# infinity-mirror-clock.net
KiCad netlist of a schematic drawn in EAGLE
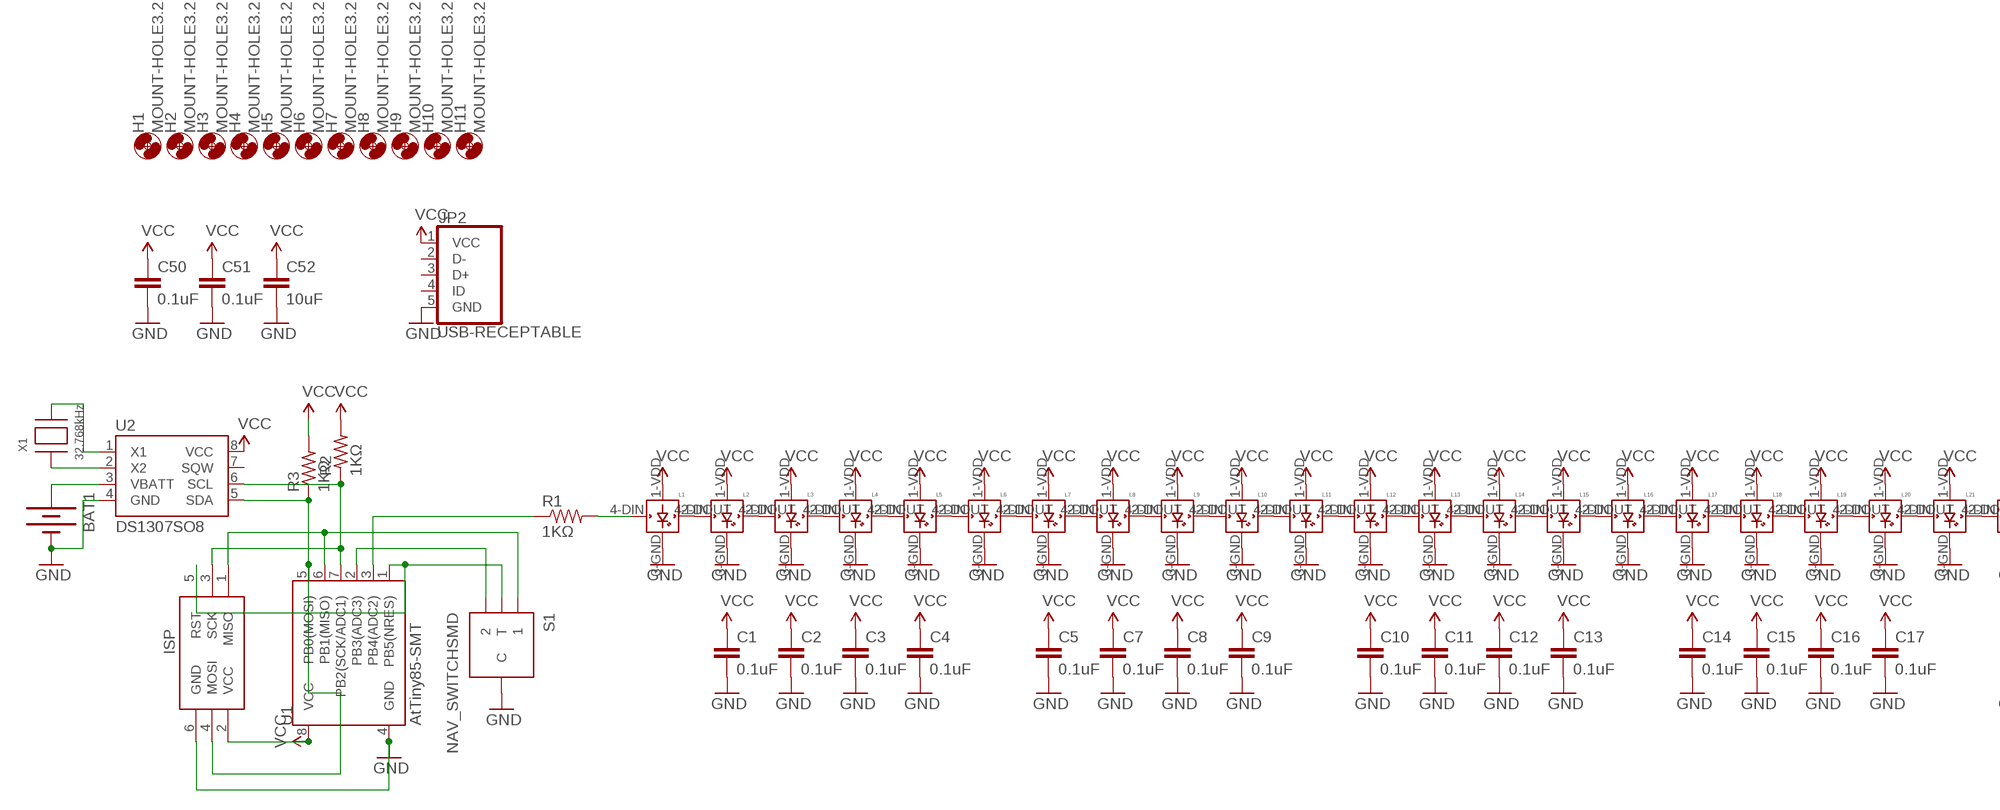
[diagram p0: schematic, sheet 1, part 1 of 2]
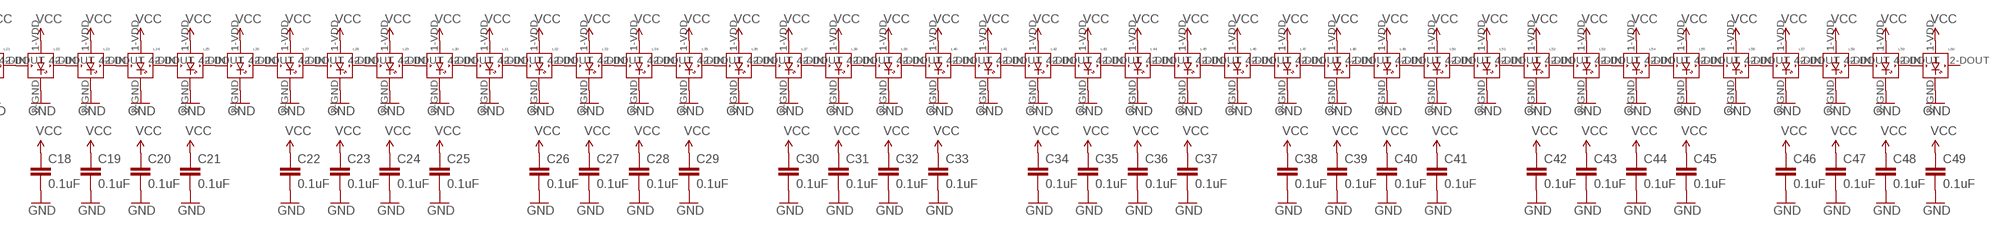
[diagram p1: schematic, sheet 1, part 2 of 2]

(export (version "E")
  (design (tool "Eeschema 10.0.6"))
  (components
    (comp (ref "BAT1")
      (value "BATTERY12MM")
      (footprint "eagle-import:BATTCON_12MM")
      (libsource (lib "eagle-import") (part "BATTERY12MM"))
    )
    (comp (ref "C1")
      (value "0.1uF")
      (footprint "eagle-import:0603-CAP")
      (libsource (lib "eagle-import") (part "0.1UF-25V-5%(0603)"))
    )
    (comp (ref "C2")
      (value "0.1uF")
      (footprint "eagle-import:0603-CAP")
      (libsource (lib "eagle-import") (part "0.1UF-25V-5%(0603)"))
    )
    (comp (ref "C3")
      (value "0.1uF")
      (footprint "eagle-import:0603-CAP")
      (libsource (lib "eagle-import") (part "0.1UF-25V-5%(0603)"))
    )
    (comp (ref "C4")
      (value "0.1uF")
      (footprint "eagle-import:0603-CAP")
      (libsource (lib "eagle-import") (part "0.1UF-25V-5%(0603)"))
    )
    (comp (ref "C5")
      (value "0.1uF")
      (footprint "eagle-import:0603-CAP")
      (libsource (lib "eagle-import") (part "0.1UF-25V-5%(0603)"))
    )
    (comp (ref "C7")
      (value "0.1uF")
      (footprint "eagle-import:0603-CAP")
      (libsource (lib "eagle-import") (part "0.1UF-25V-5%(0603)"))
    )
    (comp (ref "C8")
      (value "0.1uF")
      (footprint "eagle-import:0603-CAP")
      (libsource (lib "eagle-import") (part "0.1UF-25V-5%(0603)"))
    )
    (comp (ref "C9")
      (value "0.1uF")
      (footprint "eagle-import:0603-CAP")
      (libsource (lib "eagle-import") (part "0.1UF-25V-5%(0603)"))
    )
    (comp (ref "C10")
      (value "0.1uF")
      (footprint "eagle-import:0603-CAP")
      (libsource (lib "eagle-import") (part "0.1UF-25V-5%(0603)"))
    )
    (comp (ref "C11")
      (value "0.1uF")
      (footprint "eagle-import:0603-CAP")
      (libsource (lib "eagle-import") (part "0.1UF-25V-5%(0603)"))
    )
    (comp (ref "C12")
      (value "0.1uF")
      (footprint "eagle-import:0603-CAP")
      (libsource (lib "eagle-import") (part "0.1UF-25V-5%(0603)"))
    )
    (comp (ref "C13")
      (value "0.1uF")
      (footprint "eagle-import:0603-CAP")
      (libsource (lib "eagle-import") (part "0.1UF-25V-5%(0603)"))
    )
    (comp (ref "C14")
      (value "0.1uF")
      (footprint "eagle-import:0603-CAP")
      (libsource (lib "eagle-import") (part "0.1UF-25V-5%(0603)"))
    )
    (comp (ref "C15")
      (value "0.1uF")
      (footprint "eagle-import:0603-CAP")
      (libsource (lib "eagle-import") (part "0.1UF-25V-5%(0603)"))
    )
    (comp (ref "C16")
      (value "0.1uF")
      (footprint "eagle-import:0603-CAP")
      (libsource (lib "eagle-import") (part "0.1UF-25V-5%(0603)"))
    )
    (comp (ref "C17")
      (value "0.1uF")
      (footprint "eagle-import:0603-CAP")
      (libsource (lib "eagle-import") (part "0.1UF-25V-5%(0603)"))
    )
    (comp (ref "C18")
      (value "0.1uF")
      (footprint "eagle-import:0603-CAP")
      (libsource (lib "eagle-import") (part "0.1UF-25V-5%(0603)"))
    )
    (comp (ref "C19")
      (value "0.1uF")
      (footprint "eagle-import:0603-CAP")
      (libsource (lib "eagle-import") (part "0.1UF-25V-5%(0603)"))
    )
    (comp (ref "C20")
      (value "0.1uF")
      (footprint "eagle-import:0603-CAP")
      (libsource (lib "eagle-import") (part "0.1UF-25V-5%(0603)"))
    )
    (comp (ref "C21")
      (value "0.1uF")
      (footprint "eagle-import:0603-CAP")
      (libsource (lib "eagle-import") (part "0.1UF-25V-5%(0603)"))
    )
    (comp (ref "C22")
      (value "0.1uF")
      (footprint "eagle-import:0603-CAP")
      (libsource (lib "eagle-import") (part "0.1UF-25V-5%(0603)"))
    )
    (comp (ref "C23")
      (value "0.1uF")
      (footprint "eagle-import:0603-CAP")
      (libsource (lib "eagle-import") (part "0.1UF-25V-5%(0603)"))
    )
    (comp (ref "C24")
      (value "0.1uF")
      (footprint "eagle-import:0603-CAP")
      (libsource (lib "eagle-import") (part "0.1UF-25V-5%(0603)"))
    )
    (comp (ref "C25")
      (value "0.1uF")
      (footprint "eagle-import:0603-CAP")
      (libsource (lib "eagle-import") (part "0.1UF-25V-5%(0603)"))
    )
    (comp (ref "C26")
      (value "0.1uF")
      (footprint "eagle-import:0603-CAP")
      (libsource (lib "eagle-import") (part "0.1UF-25V-5%(0603)"))
    )
    (comp (ref "C27")
      (value "0.1uF")
      (footprint "eagle-import:0603-CAP")
      (libsource (lib "eagle-import") (part "0.1UF-25V-5%(0603)"))
    )
    (comp (ref "C28")
      (value "0.1uF")
      (footprint "eagle-import:0603-CAP")
      (libsource (lib "eagle-import") (part "0.1UF-25V-5%(0603)"))
    )
    (comp (ref "C29")
      (value "0.1uF")
      (footprint "eagle-import:0603-CAP")
      (libsource (lib "eagle-import") (part "0.1UF-25V-5%(0603)"))
    )
    (comp (ref "C30")
      (value "0.1uF")
      (footprint "eagle-import:0603-CAP")
      (libsource (lib "eagle-import") (part "0.1UF-25V-5%(0603)"))
    )
    (comp (ref "C31")
      (value "0.1uF")
      (footprint "eagle-import:0603-CAP")
      (libsource (lib "eagle-import") (part "0.1UF-25V-5%(0603)"))
    )
    (comp (ref "C32")
      (value "0.1uF")
      (footprint "eagle-import:0603-CAP")
      (libsource (lib "eagle-import") (part "0.1UF-25V-5%(0603)"))
    )
    (comp (ref "C33")
      (value "0.1uF")
      (footprint "eagle-import:0603-CAP")
      (libsource (lib "eagle-import") (part "0.1UF-25V-5%(0603)"))
    )
    (comp (ref "C34")
      (value "0.1uF")
      (footprint "eagle-import:0603-CAP")
      (libsource (lib "eagle-import") (part "0.1UF-25V-5%(0603)"))
    )
    (comp (ref "C35")
      (value "0.1uF")
      (footprint "eagle-import:0603-CAP")
      (libsource (lib "eagle-import") (part "0.1UF-25V-5%(0603)"))
    )
    (comp (ref "C36")
      (value "0.1uF")
      (footprint "eagle-import:0603-CAP")
      (libsource (lib "eagle-import") (part "0.1UF-25V-5%(0603)"))
    )
    (comp (ref "C37")
      (value "0.1uF")
      (footprint "eagle-import:0603-CAP")
      (libsource (lib "eagle-import") (part "0.1UF-25V-5%(0603)"))
    )
    (comp (ref "C38")
      (value "0.1uF")
      (footprint "eagle-import:0603-CAP")
      (libsource (lib "eagle-import") (part "0.1UF-25V-5%(0603)"))
    )
    (comp (ref "C39")
      (value "0.1uF")
      (footprint "eagle-import:0603-CAP")
      (libsource (lib "eagle-import") (part "0.1UF-25V-5%(0603)"))
    )
    (comp (ref "C40")
      (value "0.1uF")
      (footprint "eagle-import:0603-CAP")
      (libsource (lib "eagle-import") (part "0.1UF-25V-5%(0603)"))
    )
    (comp (ref "C41")
      (value "0.1uF")
      (footprint "eagle-import:0603-CAP")
      (libsource (lib "eagle-import") (part "0.1UF-25V-5%(0603)"))
    )
    (comp (ref "C42")
      (value "0.1uF")
      (footprint "eagle-import:0603-CAP")
      (libsource (lib "eagle-import") (part "0.1UF-25V-5%(0603)"))
    )
    (comp (ref "C43")
      (value "0.1uF")
      (footprint "eagle-import:0603-CAP")
      (libsource (lib "eagle-import") (part "0.1UF-25V-5%(0603)"))
    )
    (comp (ref "C44")
      (value "0.1uF")
      (footprint "eagle-import:0603-CAP")
      (libsource (lib "eagle-import") (part "0.1UF-25V-5%(0603)"))
    )
    (comp (ref "C45")
      (value "0.1uF")
      (footprint "eagle-import:0603-CAP")
      (libsource (lib "eagle-import") (part "0.1UF-25V-5%(0603)"))
    )
    (comp (ref "C46")
      (value "0.1uF")
      (footprint "eagle-import:0603-CAP")
      (libsource (lib "eagle-import") (part "0.1UF-25V-5%(0603)"))
    )
    (comp (ref "C47")
      (value "0.1uF")
      (footprint "eagle-import:0603-CAP")
      (libsource (lib "eagle-import") (part "0.1UF-25V-5%(0603)"))
    )
    (comp (ref "C48")
      (value "0.1uF")
      (footprint "eagle-import:0603-CAP")
      (libsource (lib "eagle-import") (part "0.1UF-25V-5%(0603)"))
    )
    (comp (ref "C49")
      (value "0.1uF")
      (footprint "eagle-import:0603-CAP")
      (libsource (lib "eagle-import") (part "0.1UF-25V-5%(0603)"))
    )
    (comp (ref "C50")
      (value "0.1uF")
      (footprint "eagle-import:0603-CAP")
      (libsource (lib "eagle-import") (part "0.1UF-25V-5%(0603)"))
    )
    (comp (ref "C51")
      (value "0.1uF")
      (footprint "eagle-import:0603-CAP")
      (libsource (lib "eagle-import") (part "0.1UF-25V-5%(0603)"))
    )
    (comp (ref "C52")
      (value "10uF")
      (footprint "eagle-import:0603-CAP")
      (libsource (lib "eagle-import") (part "10UF-6.3V-20%(0603)"))
    )
    (comp (ref "H1")
      (value "MOUNT-HOLE3.2")
      (footprint "eagle-import:3,2")
      (libsource (lib "eagle-import") (part "MOUNT-HOLE3.2"))
    )
    (comp (ref "H2")
      (value "MOUNT-HOLE3.2")
      (footprint "eagle-import:3,2")
      (libsource (lib "eagle-import") (part "MOUNT-HOLE3.2"))
    )
    (comp (ref "H3")
      (value "MOUNT-HOLE3.2")
      (footprint "eagle-import:3,2")
      (libsource (lib "eagle-import") (part "MOUNT-HOLE3.2"))
    )
    (comp (ref "H4")
      (value "MOUNT-HOLE3.2")
      (footprint "eagle-import:3,2")
      (libsource (lib "eagle-import") (part "MOUNT-HOLE3.2"))
    )
    (comp (ref "H5")
      (value "MOUNT-HOLE3.2")
      (footprint "eagle-import:3,2")
      (libsource (lib "eagle-import") (part "MOUNT-HOLE3.2"))
    )
    (comp (ref "H6")
      (value "MOUNT-HOLE3.2")
      (footprint "eagle-import:3,2")
      (libsource (lib "eagle-import") (part "MOUNT-HOLE3.2"))
    )
    (comp (ref "H7")
      (value "MOUNT-HOLE3.2")
      (footprint "eagle-import:3,2")
      (libsource (lib "eagle-import") (part "MOUNT-HOLE3.2"))
    )
    (comp (ref "H8")
      (value "MOUNT-HOLE3.2")
      (footprint "eagle-import:3,2")
      (libsource (lib "eagle-import") (part "MOUNT-HOLE3.2"))
    )
    (comp (ref "H9")
      (value "MOUNT-HOLE3.2")
      (footprint "eagle-import:3,2")
      (libsource (lib "eagle-import") (part "MOUNT-HOLE3.2"))
    )
    (comp (ref "H10")
      (value "MOUNT-HOLE3.2")
      (footprint "eagle-import:3,2")
      (libsource (lib "eagle-import") (part "MOUNT-HOLE3.2"))
    )
    (comp (ref "H11")
      (value "MOUNT-HOLE3.2")
      (footprint "eagle-import:3,2")
      (libsource (lib "eagle-import") (part "MOUNT-HOLE3.2"))
    )
    (comp (ref "ISP")
      (value "AVRISPAVRSMTISP")
      (footprint "eagle-import:AVRSMTISP")
      (libsource (lib "eagle-import") (part "AVRISPAVRSMTISP"))
    )
    (comp (ref "JP2")
      (value "USB-RECEPTABLE")
      (footprint "eagle-import:FCI-10103594-0001LF")
      (libsource (lib "eagle-import") (part "USB-RECEPTABLE"))
    )
    (comp (ref "L1")
      (value "WS2812B")
      (footprint "eagle-import:WS2812B")
      (libsource (lib "eagle-import") (part "WS2812B"))
    )
    (comp (ref "L2")
      (value "WS2812B")
      (footprint "eagle-import:WS2812B")
      (libsource (lib "eagle-import") (part "WS2812B"))
    )
    (comp (ref "L3")
      (value "WS2812B")
      (footprint "eagle-import:WS2812B")
      (libsource (lib "eagle-import") (part "WS2812B"))
    )
    (comp (ref "L4")
      (value "WS2812B")
      (footprint "eagle-import:WS2812B")
      (libsource (lib "eagle-import") (part "WS2812B"))
    )
    (comp (ref "L5")
      (value "WS2812B")
      (footprint "eagle-import:WS2812B")
      (libsource (lib "eagle-import") (part "WS2812B"))
    )
    (comp (ref "L6")
      (value "WS2812B")
      (footprint "eagle-import:WS2812B")
      (libsource (lib "eagle-import") (part "WS2812B"))
    )
    (comp (ref "L7")
      (value "WS2812B")
      (footprint "eagle-import:WS2812B")
      (libsource (lib "eagle-import") (part "WS2812B"))
    )
    (comp (ref "L8")
      (value "WS2812B")
      (footprint "eagle-import:WS2812B")
      (libsource (lib "eagle-import") (part "WS2812B"))
    )
    (comp (ref "L9")
      (value "WS2812B")
      (footprint "eagle-import:WS2812B")
      (libsource (lib "eagle-import") (part "WS2812B"))
    )
    (comp (ref "L10")
      (value "WS2812B")
      (footprint "eagle-import:WS2812B")
      (libsource (lib "eagle-import") (part "WS2812B"))
    )
    (comp (ref "L11")
      (value "WS2812B")
      (footprint "eagle-import:WS2812B")
      (libsource (lib "eagle-import") (part "WS2812B"))
    )
    (comp (ref "L12")
      (value "WS2812B")
      (footprint "eagle-import:WS2812B")
      (libsource (lib "eagle-import") (part "WS2812B"))
    )
    (comp (ref "L13")
      (value "WS2812B")
      (footprint "eagle-import:WS2812B")
      (libsource (lib "eagle-import") (part "WS2812B"))
    )
    (comp (ref "L14")
      (value "WS2812B")
      (footprint "eagle-import:WS2812B")
      (libsource (lib "eagle-import") (part "WS2812B"))
    )
    (comp (ref "L15")
      (value "WS2812B")
      (footprint "eagle-import:WS2812B")
      (libsource (lib "eagle-import") (part "WS2812B"))
    )
    (comp (ref "L16")
      (value "WS2812B")
      (footprint "eagle-import:WS2812B")
      (libsource (lib "eagle-import") (part "WS2812B"))
    )
    (comp (ref "L17")
      (value "WS2812B")
      (footprint "eagle-import:WS2812B")
      (libsource (lib "eagle-import") (part "WS2812B"))
    )
    (comp (ref "L18")
      (value "WS2812B")
      (footprint "eagle-import:WS2812B")
      (libsource (lib "eagle-import") (part "WS2812B"))
    )
    (comp (ref "L19")
      (value "WS2812B")
      (footprint "eagle-import:WS2812B")
      (libsource (lib "eagle-import") (part "WS2812B"))
    )
    (comp (ref "L20")
      (value "WS2812B")
      (footprint "eagle-import:WS2812B")
      (libsource (lib "eagle-import") (part "WS2812B"))
    )
    (comp (ref "L21")
      (value "WS2812B")
      (footprint "eagle-import:WS2812B")
      (libsource (lib "eagle-import") (part "WS2812B"))
    )
    (comp (ref "L22")
      (value "WS2812B")
      (footprint "eagle-import:WS2812B")
      (libsource (lib "eagle-import") (part "WS2812B"))
    )
    (comp (ref "L23")
      (value "WS2812B")
      (footprint "eagle-import:WS2812B")
      (libsource (lib "eagle-import") (part "WS2812B"))
    )
    (comp (ref "L24")
      (value "WS2812B")
      (footprint "eagle-import:WS2812B")
      (libsource (lib "eagle-import") (part "WS2812B"))
    )
    (comp (ref "L25")
      (value "WS2812B")
      (footprint "eagle-import:WS2812B")
      (libsource (lib "eagle-import") (part "WS2812B"))
    )
    (comp (ref "L26")
      (value "WS2812B")
      (footprint "eagle-import:WS2812B")
      (libsource (lib "eagle-import") (part "WS2812B"))
    )
    (comp (ref "L27")
      (value "WS2812B")
      (footprint "eagle-import:WS2812B")
      (libsource (lib "eagle-import") (part "WS2812B"))
    )
    (comp (ref "L28")
      (value "WS2812B")
      (footprint "eagle-import:WS2812B")
      (libsource (lib "eagle-import") (part "WS2812B"))
    )
    (comp (ref "L29")
      (value "WS2812B")
      (footprint "eagle-import:WS2812B")
      (libsource (lib "eagle-import") (part "WS2812B"))
    )
    (comp (ref "L30")
      (value "WS2812B")
      (footprint "eagle-import:WS2812B")
      (libsource (lib "eagle-import") (part "WS2812B"))
    )
    (comp (ref "L31")
      (value "WS2812B")
      (footprint "eagle-import:WS2812B")
      (libsource (lib "eagle-import") (part "WS2812B"))
    )
    (comp (ref "L32")
      (value "WS2812B")
      (footprint "eagle-import:WS2812B")
      (libsource (lib "eagle-import") (part "WS2812B"))
    )
    (comp (ref "L33")
      (value "WS2812B")
      (footprint "eagle-import:WS2812B")
      (libsource (lib "eagle-import") (part "WS2812B"))
    )
    (comp (ref "L34")
      (value "WS2812B")
      (footprint "eagle-import:WS2812B")
      (libsource (lib "eagle-import") (part "WS2812B"))
    )
    (comp (ref "L35")
      (value "WS2812B")
      (footprint "eagle-import:WS2812B")
      (libsource (lib "eagle-import") (part "WS2812B"))
    )
    (comp (ref "L36")
      (value "WS2812B")
      (footprint "eagle-import:WS2812B")
      (libsource (lib "eagle-import") (part "WS2812B"))
    )
    (comp (ref "L37")
      (value "WS2812B")
      (footprint "eagle-import:WS2812B")
      (libsource (lib "eagle-import") (part "WS2812B"))
    )
    (comp (ref "L38")
      (value "WS2812B")
      (footprint "eagle-import:WS2812B")
      (libsource (lib "eagle-import") (part "WS2812B"))
    )
    (comp (ref "L39")
      (value "WS2812B")
      (footprint "eagle-import:WS2812B")
      (libsource (lib "eagle-import") (part "WS2812B"))
    )
    (comp (ref "L40")
      (value "WS2812B")
      (footprint "eagle-import:WS2812B")
      (libsource (lib "eagle-import") (part "WS2812B"))
    )
    (comp (ref "L41")
      (value "WS2812B")
      (footprint "eagle-import:WS2812B")
      (libsource (lib "eagle-import") (part "WS2812B"))
    )
    (comp (ref "L42")
      (value "WS2812B")
      (footprint "eagle-import:WS2812B")
      (libsource (lib "eagle-import") (part "WS2812B"))
    )
    (comp (ref "L43")
      (value "WS2812B")
      (footprint "eagle-import:WS2812B")
      (libsource (lib "eagle-import") (part "WS2812B"))
    )
    (comp (ref "L44")
      (value "WS2812B")
      (footprint "eagle-import:WS2812B")
      (libsource (lib "eagle-import") (part "WS2812B"))
    )
    (comp (ref "L45")
      (value "WS2812B")
      (footprint "eagle-import:WS2812B")
      (libsource (lib "eagle-import") (part "WS2812B"))
    )
    (comp (ref "L46")
      (value "WS2812B")
      (footprint "eagle-import:WS2812B")
      (libsource (lib "eagle-import") (part "WS2812B"))
    )
    (comp (ref "L47")
      (value "WS2812B")
      (footprint "eagle-import:WS2812B")
      (libsource (lib "eagle-import") (part "WS2812B"))
    )
    (comp (ref "L48")
      (value "WS2812B")
      (footprint "eagle-import:WS2812B")
      (libsource (lib "eagle-import") (part "WS2812B"))
    )
    (comp (ref "L49")
      (value "WS2812B")
      (footprint "eagle-import:WS2812B")
      (libsource (lib "eagle-import") (part "WS2812B"))
    )
    (comp (ref "L50")
      (value "WS2812B")
      (footprint "eagle-import:WS2812B")
      (libsource (lib "eagle-import") (part "WS2812B"))
    )
    (comp (ref "L51")
      (value "WS2812B")
      (footprint "eagle-import:WS2812B")
      (libsource (lib "eagle-import") (part "WS2812B"))
    )
    (comp (ref "L52")
      (value "WS2812B")
      (footprint "eagle-import:WS2812B")
      (libsource (lib "eagle-import") (part "WS2812B"))
    )
    (comp (ref "L53")
      (value "WS2812B")
      (footprint "eagle-import:WS2812B")
      (libsource (lib "eagle-import") (part "WS2812B"))
    )
    (comp (ref "L54")
      (value "WS2812B")
      (footprint "eagle-import:WS2812B")
      (libsource (lib "eagle-import") (part "WS2812B"))
    )
    (comp (ref "L55")
      (value "WS2812B")
      (footprint "eagle-import:WS2812B")
      (libsource (lib "eagle-import") (part "WS2812B"))
    )
    (comp (ref "L56")
      (value "WS2812B")
      (footprint "eagle-import:WS2812B")
      (libsource (lib "eagle-import") (part "WS2812B"))
    )
    (comp (ref "L57")
      (value "WS2812B")
      (footprint "eagle-import:WS2812B")
      (libsource (lib "eagle-import") (part "WS2812B"))
    )
    (comp (ref "L58")
      (value "WS2812B")
      (footprint "eagle-import:WS2812B")
      (libsource (lib "eagle-import") (part "WS2812B"))
    )
    (comp (ref "L59")
      (value "WS2812B")
      (footprint "eagle-import:WS2812B")
      (libsource (lib "eagle-import") (part "WS2812B"))
    )
    (comp (ref "L60")
      (value "WS2812B")
      (footprint "eagle-import:WS2812B")
      (libsource (lib "eagle-import") (part "WS2812B"))
    )
    (comp (ref "R1")
      (value "1KΩ")
      (footprint "eagle-import:0603-RES")
      (libsource (lib "eagle-import") (part "680OHM1/10W5%(0603)"))
    )
    (comp (ref "R2")
      (value "1KΩ")
      (footprint "eagle-import:R0603")
      (libsource (lib "eagle-import") (part "R-US_R0603"))
    )
    (comp (ref "R3")
      (value "1KΩ")
      (footprint "eagle-import:R0603")
      (libsource (lib "eagle-import") (part "R-US_R0603"))
    )
    (comp (ref "S1")
      (value "NAV_SWITCHSMD")
      (footprint "eagle-import:NAV_SWITCH")
      (libsource (lib "eagle-import") (part "NAV_SWITCHSMD"))
    )
    (comp (ref "U1")
      (value "AtTiny85-SMT")
      (footprint "eagle-import:SO08-EIAJ")
      (libsource (lib "eagle-import") (part "ATTINY45TINY45-20-SMT"))
    )
    (comp (ref "U2")
      (value "DS1307SO8")
      (footprint "eagle-import:SO08")
      (libsource (lib "eagle-import") (part "DS1307SO8"))
    )
    (comp (ref "X1")
      (value "32.768kHz")
      (footprint "eagle-import:XTAL3215")
      (libsource (lib "eagle-import") (part "XTAL-3.2X1.5"))
    )
  )
  (nets
    (net (code "1") (name "GND") (class "Default")
      (node (ref "BAT1") (pin "GND") (pinfunction "-_GND") (pintype "power_in"))
      (node (ref "C1") (pin "2") (pinfunction "2_2") (pintype "passive"))
      (node (ref "C10") (pin "2") (pinfunction "2_2") (pintype "passive"))
      (node (ref "C11") (pin "2") (pinfunction "2_2") (pintype "passive"))
      (node (ref "C12") (pin "2") (pinfunction "2_2") (pintype "passive"))
      (node (ref "C13") (pin "2") (pinfunction "2_2") (pintype "passive"))
      (node (ref "C14") (pin "2") (pinfunction "2_2") (pintype "passive"))
      (node (ref "C15") (pin "2") (pinfunction "2_2") (pintype "passive"))
      (node (ref "C16") (pin "2") (pinfunction "2_2") (pintype "passive"))
      (node (ref "C17") (pin "2") (pinfunction "2_2") (pintype "passive"))
      (node (ref "C18") (pin "2") (pinfunction "2_2") (pintype "passive"))
      (node (ref "C19") (pin "2") (pinfunction "2_2") (pintype "passive"))
      (node (ref "C2") (pin "2") (pinfunction "2_2") (pintype "passive"))
      (node (ref "C20") (pin "2") (pinfunction "2_2") (pintype "passive"))
      (node (ref "C21") (pin "2") (pinfunction "2_2") (pintype "passive"))
      (node (ref "C22") (pin "2") (pinfunction "2_2") (pintype "passive"))
      (node (ref "C23") (pin "2") (pinfunction "2_2") (pintype "passive"))
      (node (ref "C24") (pin "2") (pinfunction "2_2") (pintype "passive"))
      (node (ref "C25") (pin "2") (pinfunction "2_2") (pintype "passive"))
      (node (ref "C26") (pin "2") (pinfunction "2_2") (pintype "passive"))
      (node (ref "C27") (pin "2") (pinfunction "2_2") (pintype "passive"))
      (node (ref "C28") (pin "2") (pinfunction "2_2") (pintype "passive"))
      (node (ref "C29") (pin "2") (pinfunction "2_2") (pintype "passive"))
      (node (ref "C3") (pin "2") (pinfunction "2_2") (pintype "passive"))
      (node (ref "C30") (pin "2") (pinfunction "2_2") (pintype "passive"))
      (node (ref "C31") (pin "2") (pinfunction "2_2") (pintype "passive"))
      (node (ref "C32") (pin "2") (pinfunction "2_2") (pintype "passive"))
      (node (ref "C33") (pin "2") (pinfunction "2_2") (pintype "passive"))
      (node (ref "C34") (pin "2") (pinfunction "2_2") (pintype "passive"))
      (node (ref "C35") (pin "2") (pinfunction "2_2") (pintype "passive"))
      (node (ref "C36") (pin "2") (pinfunction "2_2") (pintype "passive"))
      (node (ref "C37") (pin "2") (pinfunction "2_2") (pintype "passive"))
      (node (ref "C38") (pin "2") (pinfunction "2_2") (pintype "passive"))
      (node (ref "C39") (pin "2") (pinfunction "2_2") (pintype "passive"))
      (node (ref "C4") (pin "2") (pinfunction "2_2") (pintype "passive"))
      (node (ref "C40") (pin "2") (pinfunction "2_2") (pintype "passive"))
      (node (ref "C41") (pin "2") (pinfunction "2_2") (pintype "passive"))
      (node (ref "C42") (pin "2") (pinfunction "2_2") (pintype "passive"))
      (node (ref "C43") (pin "2") (pinfunction "2_2") (pintype "passive"))
      (node (ref "C44") (pin "2") (pinfunction "2_2") (pintype "passive"))
      (node (ref "C45") (pin "2") (pinfunction "2_2") (pintype "passive"))
      (node (ref "C46") (pin "2") (pinfunction "2_2") (pintype "passive"))
      (node (ref "C47") (pin "2") (pinfunction "2_2") (pintype "passive"))
      (node (ref "C48") (pin "2") (pinfunction "2_2") (pintype "passive"))
      (node (ref "C49") (pin "2") (pinfunction "2_2") (pintype "passive"))
      (node (ref "C5") (pin "2") (pinfunction "2_2") (pintype "passive"))
      (node (ref "C50") (pin "2") (pinfunction "2_2") (pintype "passive"))
      (node (ref "C51") (pin "2") (pinfunction "2_2") (pintype "passive"))
      (node (ref "C52") (pin "2") (pinfunction "2_2") (pintype "passive"))
      (node (ref "C7") (pin "2") (pinfunction "2_2") (pintype "passive"))
      (node (ref "C8") (pin "2") (pinfunction "2_2") (pintype "passive"))
      (node (ref "C9") (pin "2") (pinfunction "2_2") (pintype "passive"))
      (node (ref "ISP") (pin "6") (pinfunction "GND_6") (pintype "power_in"))
      (node (ref "JP2") (pin "5") (pinfunction "GND_5") (pintype "bidirectional"))
      (node (ref "L1") (pin "3-GND") (pinfunction "GND_3-GND") (pintype "bidirectional"))
      (node (ref "L10") (pin "3-GND") (pinfunction "GND_3-GND") (pintype "bidirectional"))
      (node (ref "L11") (pin "3-GND") (pinfunction "GND_3-GND") (pintype "bidirectional"))
      (node (ref "L12") (pin "3-GND") (pinfunction "GND_3-GND") (pintype "bidirectional"))
      (node (ref "L13") (pin "3-GND") (pinfunction "GND_3-GND") (pintype "bidirectional"))
      (node (ref "L14") (pin "3-GND") (pinfunction "GND_3-GND") (pintype "bidirectional"))
      (node (ref "L15") (pin "3-GND") (pinfunction "GND_3-GND") (pintype "bidirectional"))
      (node (ref "L16") (pin "3-GND") (pinfunction "GND_3-GND") (pintype "bidirectional"))
      (node (ref "L17") (pin "3-GND") (pinfunction "GND_3-GND") (pintype "bidirectional"))
      (node (ref "L18") (pin "3-GND") (pinfunction "GND_3-GND") (pintype "bidirectional"))
      (node (ref "L19") (pin "3-GND") (pinfunction "GND_3-GND") (pintype "bidirectional"))
      (node (ref "L2") (pin "3-GND") (pinfunction "GND_3-GND") (pintype "bidirectional"))
      (node (ref "L20") (pin "3-GND") (pinfunction "GND_3-GND") (pintype "bidirectional"))
      (node (ref "L21") (pin "3-GND") (pinfunction "GND_3-GND") (pintype "bidirectional"))
      (node (ref "L22") (pin "3-GND") (pinfunction "GND_3-GND") (pintype "bidirectional"))
      (node (ref "L23") (pin "3-GND") (pinfunction "GND_3-GND") (pintype "bidirectional"))
      (node (ref "L24") (pin "3-GND") (pinfunction "GND_3-GND") (pintype "bidirectional"))
      (node (ref "L25") (pin "3-GND") (pinfunction "GND_3-GND") (pintype "bidirectional"))
      (node (ref "L26") (pin "3-GND") (pinfunction "GND_3-GND") (pintype "bidirectional"))
      (node (ref "L27") (pin "3-GND") (pinfunction "GND_3-GND") (pintype "bidirectional"))
      (node (ref "L28") (pin "3-GND") (pinfunction "GND_3-GND") (pintype "bidirectional"))
      (node (ref "L29") (pin "3-GND") (pinfunction "GND_3-GND") (pintype "bidirectional"))
      (node (ref "L3") (pin "3-GND") (pinfunction "GND_3-GND") (pintype "bidirectional"))
      (node (ref "L30") (pin "3-GND") (pinfunction "GND_3-GND") (pintype "bidirectional"))
      (node (ref "L31") (pin "3-GND") (pinfunction "GND_3-GND") (pintype "bidirectional"))
      (node (ref "L32") (pin "3-GND") (pinfunction "GND_3-GND") (pintype "bidirectional"))
      (node (ref "L33") (pin "3-GND") (pinfunction "GND_3-GND") (pintype "bidirectional"))
      (node (ref "L34") (pin "3-GND") (pinfunction "GND_3-GND") (pintype "bidirectional"))
      (node (ref "L35") (pin "3-GND") (pinfunction "GND_3-GND") (pintype "bidirectional"))
      (node (ref "L36") (pin "3-GND") (pinfunction "GND_3-GND") (pintype "bidirectional"))
      (node (ref "L37") (pin "3-GND") (pinfunction "GND_3-GND") (pintype "bidirectional"))
      (node (ref "L38") (pin "3-GND") (pinfunction "GND_3-GND") (pintype "bidirectional"))
      (node (ref "L39") (pin "3-GND") (pinfunction "GND_3-GND") (pintype "bidirectional"))
      (node (ref "L4") (pin "3-GND") (pinfunction "GND_3-GND") (pintype "bidirectional"))
      (node (ref "L40") (pin "3-GND") (pinfunction "GND_3-GND") (pintype "bidirectional"))
      (node (ref "L41") (pin "3-GND") (pinfunction "GND_3-GND") (pintype "bidirectional"))
      (node (ref "L42") (pin "3-GND") (pinfunction "GND_3-GND") (pintype "bidirectional"))
      (node (ref "L43") (pin "3-GND") (pinfunction "GND_3-GND") (pintype "bidirectional"))
      (node (ref "L44") (pin "3-GND") (pinfunction "GND_3-GND") (pintype "bidirectional"))
      (node (ref "L45") (pin "3-GND") (pinfunction "GND_3-GND") (pintype "bidirectional"))
      (node (ref "L46") (pin "3-GND") (pinfunction "GND_3-GND") (pintype "bidirectional"))
      (node (ref "L47") (pin "3-GND") (pinfunction "GND_3-GND") (pintype "bidirectional"))
      (node (ref "L48") (pin "3-GND") (pinfunction "GND_3-GND") (pintype "bidirectional"))
      (node (ref "L49") (pin "3-GND") (pinfunction "GND_3-GND") (pintype "bidirectional"))
      (node (ref "L5") (pin "3-GND") (pinfunction "GND_3-GND") (pintype "bidirectional"))
      (node (ref "L50") (pin "3-GND") (pinfunction "GND_3-GND") (pintype "bidirectional"))
      (node (ref "L51") (pin "3-GND") (pinfunction "GND_3-GND") (pintype "bidirectional"))
      (node (ref "L52") (pin "3-GND") (pinfunction "GND_3-GND") (pintype "bidirectional"))
      (node (ref "L53") (pin "3-GND") (pinfunction "GND_3-GND") (pintype "bidirectional"))
      (node (ref "L54") (pin "3-GND") (pinfunction "GND_3-GND") (pintype "bidirectional"))
      (node (ref "L55") (pin "3-GND") (pinfunction "GND_3-GND") (pintype "bidirectional"))
      (node (ref "L56") (pin "3-GND") (pinfunction "GND_3-GND") (pintype "bidirectional"))
      (node (ref "L57") (pin "3-GND") (pinfunction "GND_3-GND") (pintype "bidirectional"))
      (node (ref "L58") (pin "3-GND") (pinfunction "GND_3-GND") (pintype "bidirectional"))
      (node (ref "L59") (pin "3-GND") (pinfunction "GND_3-GND") (pintype "bidirectional"))
      (node (ref "L6") (pin "3-GND") (pinfunction "GND_3-GND") (pintype "bidirectional"))
      (node (ref "L60") (pin "3-GND") (pinfunction "GND_3-GND") (pintype "bidirectional"))
      (node (ref "L7") (pin "3-GND") (pinfunction "GND_3-GND") (pintype "bidirectional"))
      (node (ref "L8") (pin "3-GND") (pinfunction "GND_3-GND") (pintype "bidirectional"))
      (node (ref "L9") (pin "3-GND") (pinfunction "GND_3-GND") (pintype "bidirectional"))
      (node (ref "S1") (pin "C") (pinfunction "C_C") (pintype "power_in"))
      (node (ref "U1") (pin "4") (pinfunction "GND_4") (pintype "bidirectional"))
      (node (ref "U2") (pin "4") (pinfunction "GND_4") (pintype "bidirectional"))
    )
    (net (code "2") (name "Net-(BAT1-+)") (class "Default")
      (node (ref "BAT1") (pin "PWR@1") (pinfunction "+_PWR@1") (pintype "power_in"))
      (node (ref "U2") (pin "3") (pinfunction "VBATT_3") (pintype "bidirectional"))
    )
    (net (code "3") (name "Net-(ISP-MISO)") (class "Default")
      (node (ref "ISP") (pin "1") (pinfunction "MISO_1") (pintype "input"))
      (node (ref "S1") (pin "1") (pinfunction "1_1") (pintype "input"))
      (node (ref "U1") (pin "6") (pinfunction "PB1(MISO)_6") (pintype "bidirectional"))
    )
    (net (code "4") (name "Net-(ISP-MOSI)") (class "Default")
      (node (ref "ISP") (pin "4") (pinfunction "MOSI_4") (pintype "output"))
      (node (ref "R3") (pin "1") (pinfunction "1_1") (pintype "passive"))
      (node (ref "U1") (pin "5") (pinfunction "PB0(MOSI)_5") (pintype "bidirectional"))
      (node (ref "U2") (pin "5") (pinfunction "SDA_5") (pintype "bidirectional"))
    )
    (net (code "5") (name "Net-(ISP-RST)") (class "Default")
      (node (ref "ISP") (pin "5") (pinfunction "RST_5") (pintype "output"))
      (node (ref "S1") (pin "T") (pinfunction "T_T") (pintype "input"))
      (node (ref "U1") (pin "1") (pinfunction "PB5(NRES)_1") (pintype "bidirectional"))
    )
    (net (code "6") (name "Net-(ISP-SCK)") (class "Default")
      (node (ref "ISP") (pin "3") (pinfunction "SCK_3") (pintype "output"))
      (node (ref "R2") (pin "1") (pinfunction "1_1") (pintype "passive"))
      (node (ref "U1") (pin "7") (pinfunction "PB2(SCK/ADC1)_7") (pintype "bidirectional"))
      (node (ref "U2") (pin "6") (pinfunction "SCL_6") (pintype "bidirectional"))
    )
    (net (code "7") (name "Net-(L1-DIN)") (class "Default")
      (node (ref "L1") (pin "4-DIN") (pinfunction "DIN_4-DIN") (pintype "input"))
      (node (ref "R1") (pin "2") (pinfunction "2_2") (pintype "passive"))
    )
    (net (code "8") (name "Net-(L1-DOUT)") (class "Default")
      (node (ref "L1") (pin "2-DOUT") (pinfunction "DOUT_2-DOUT") (pintype "output"))
      (node (ref "L2") (pin "4-DIN") (pinfunction "DIN_4-DIN") (pintype "input"))
    )
    (net (code "9") (name "Net-(L2-DOUT)") (class "Default")
      (node (ref "L2") (pin "2-DOUT") (pinfunction "DOUT_2-DOUT") (pintype "output"))
      (node (ref "L3") (pin "4-DIN") (pinfunction "DIN_4-DIN") (pintype "input"))
    )
    (net (code "10") (name "Net-(L3-DOUT)") (class "Default")
      (node (ref "L3") (pin "2-DOUT") (pinfunction "DOUT_2-DOUT") (pintype "output"))
      (node (ref "L4") (pin "4-DIN") (pinfunction "DIN_4-DIN") (pintype "input"))
    )
    (net (code "11") (name "Net-(L4-DOUT)") (class "Default")
      (node (ref "L4") (pin "2-DOUT") (pinfunction "DOUT_2-DOUT") (pintype "output"))
      (node (ref "L5") (pin "4-DIN") (pinfunction "DIN_4-DIN") (pintype "input"))
    )
    (net (code "12") (name "Net-(L5-DOUT)") (class "Default")
      (node (ref "L5") (pin "2-DOUT") (pinfunction "DOUT_2-DOUT") (pintype "output"))
      (node (ref "L6") (pin "4-DIN") (pinfunction "DIN_4-DIN") (pintype "input"))
    )
    (net (code "13") (name "Net-(L6-DOUT)") (class "Default")
      (node (ref "L6") (pin "2-DOUT") (pinfunction "DOUT_2-DOUT") (pintype "output"))
      (node (ref "L7") (pin "4-DIN") (pinfunction "DIN_4-DIN") (pintype "input"))
    )
    (net (code "14") (name "Net-(L7-DOUT)") (class "Default")
      (node (ref "L7") (pin "2-DOUT") (pinfunction "DOUT_2-DOUT") (pintype "output"))
      (node (ref "L8") (pin "4-DIN") (pinfunction "DIN_4-DIN") (pintype "input"))
    )
    (net (code "15") (name "Net-(L8-DOUT)") (class "Default")
      (node (ref "L8") (pin "2-DOUT") (pinfunction "DOUT_2-DOUT") (pintype "output"))
      (node (ref "L9") (pin "4-DIN") (pinfunction "DIN_4-DIN") (pintype "input"))
    )
    (net (code "16") (name "Net-(L10-DIN)") (class "Default")
      (node (ref "L10") (pin "4-DIN") (pinfunction "DIN_4-DIN") (pintype "input"))
      (node (ref "L9") (pin "2-DOUT") (pinfunction "DOUT_2-DOUT") (pintype "output"))
    )
    (net (code "17") (name "Net-(L10-DOUT)") (class "Default")
      (node (ref "L10") (pin "2-DOUT") (pinfunction "DOUT_2-DOUT") (pintype "output"))
      (node (ref "L11") (pin "4-DIN") (pinfunction "DIN_4-DIN") (pintype "input"))
    )
    (net (code "18") (name "Net-(L11-DOUT)") (class "Default")
      (node (ref "L11") (pin "2-DOUT") (pinfunction "DOUT_2-DOUT") (pintype "output"))
      (node (ref "L12") (pin "4-DIN") (pinfunction "DIN_4-DIN") (pintype "input"))
    )
    (net (code "19") (name "Net-(L12-DOUT)") (class "Default")
      (node (ref "L12") (pin "2-DOUT") (pinfunction "DOUT_2-DOUT") (pintype "output"))
      (node (ref "L13") (pin "4-DIN") (pinfunction "DIN_4-DIN") (pintype "input"))
    )
    (net (code "20") (name "Net-(L13-DOUT)") (class "Default")
      (node (ref "L13") (pin "2-DOUT") (pinfunction "DOUT_2-DOUT") (pintype "output"))
      (node (ref "L14") (pin "4-DIN") (pinfunction "DIN_4-DIN") (pintype "input"))
    )
    (net (code "21") (name "Net-(L14-DOUT)") (class "Default")
      (node (ref "L14") (pin "2-DOUT") (pinfunction "DOUT_2-DOUT") (pintype "output"))
      (node (ref "L15") (pin "4-DIN") (pinfunction "DIN_4-DIN") (pintype "input"))
    )
    (net (code "22") (name "Net-(L15-DOUT)") (class "Default")
      (node (ref "L15") (pin "2-DOUT") (pinfunction "DOUT_2-DOUT") (pintype "output"))
      (node (ref "L16") (pin "4-DIN") (pinfunction "DIN_4-DIN") (pintype "input"))
    )
    (net (code "23") (name "Net-(L16-DOUT)") (class "Default")
      (node (ref "L16") (pin "2-DOUT") (pinfunction "DOUT_2-DOUT") (pintype "output"))
      (node (ref "L17") (pin "4-DIN") (pinfunction "DIN_4-DIN") (pintype "input"))
    )
    (net (code "24") (name "Net-(L17-DOUT)") (class "Default")
      (node (ref "L17") (pin "2-DOUT") (pinfunction "DOUT_2-DOUT") (pintype "output"))
      (node (ref "L18") (pin "4-DIN") (pinfunction "DIN_4-DIN") (pintype "input"))
    )
    (net (code "25") (name "Net-(L18-DOUT)") (class "Default")
      (node (ref "L18") (pin "2-DOUT") (pinfunction "DOUT_2-DOUT") (pintype "output"))
      (node (ref "L19") (pin "4-DIN") (pinfunction "DIN_4-DIN") (pintype "input"))
    )
    (net (code "26") (name "Net-(L19-DOUT)") (class "Default")
      (node (ref "L19") (pin "2-DOUT") (pinfunction "DOUT_2-DOUT") (pintype "output"))
      (node (ref "L20") (pin "4-DIN") (pinfunction "DIN_4-DIN") (pintype "input"))
    )
    (net (code "27") (name "Net-(L20-DOUT)") (class "Default")
      (node (ref "L20") (pin "2-DOUT") (pinfunction "DOUT_2-DOUT") (pintype "output"))
      (node (ref "L21") (pin "4-DIN") (pinfunction "DIN_4-DIN") (pintype "input"))
    )
    (net (code "28") (name "Net-(L21-DOUT)") (class "Default")
      (node (ref "L21") (pin "2-DOUT") (pinfunction "DOUT_2-DOUT") (pintype "output"))
      (node (ref "L22") (pin "4-DIN") (pinfunction "DIN_4-DIN") (pintype "input"))
    )
    (net (code "29") (name "Net-(L22-DOUT)") (class "Default")
      (node (ref "L22") (pin "2-DOUT") (pinfunction "DOUT_2-DOUT") (pintype "output"))
      (node (ref "L23") (pin "4-DIN") (pinfunction "DIN_4-DIN") (pintype "input"))
    )
    (net (code "30") (name "Net-(L23-DOUT)") (class "Default")
      (node (ref "L23") (pin "2-DOUT") (pinfunction "DOUT_2-DOUT") (pintype "output"))
      (node (ref "L24") (pin "4-DIN") (pinfunction "DIN_4-DIN") (pintype "input"))
    )
    (net (code "31") (name "Net-(L24-DOUT)") (class "Default")
      (node (ref "L24") (pin "2-DOUT") (pinfunction "DOUT_2-DOUT") (pintype "output"))
      (node (ref "L25") (pin "4-DIN") (pinfunction "DIN_4-DIN") (pintype "input"))
    )
    (net (code "32") (name "Net-(L25-DOUT)") (class "Default")
      (node (ref "L25") (pin "2-DOUT") (pinfunction "DOUT_2-DOUT") (pintype "output"))
      (node (ref "L26") (pin "4-DIN") (pinfunction "DIN_4-DIN") (pintype "input"))
    )
    (net (code "33") (name "Net-(L26-DOUT)") (class "Default")
      (node (ref "L26") (pin "2-DOUT") (pinfunction "DOUT_2-DOUT") (pintype "output"))
      (node (ref "L27") (pin "4-DIN") (pinfunction "DIN_4-DIN") (pintype "input"))
    )
    (net (code "34") (name "Net-(L27-DOUT)") (class "Default")
      (node (ref "L27") (pin "2-DOUT") (pinfunction "DOUT_2-DOUT") (pintype "output"))
      (node (ref "L28") (pin "4-DIN") (pinfunction "DIN_4-DIN") (pintype "input"))
    )
    (net (code "35") (name "Net-(L28-DOUT)") (class "Default")
      (node (ref "L28") (pin "2-DOUT") (pinfunction "DOUT_2-DOUT") (pintype "output"))
      (node (ref "L29") (pin "4-DIN") (pinfunction "DIN_4-DIN") (pintype "input"))
    )
    (net (code "36") (name "Net-(L29-DOUT)") (class "Default")
      (node (ref "L29") (pin "2-DOUT") (pinfunction "DOUT_2-DOUT") (pintype "output"))
      (node (ref "L30") (pin "4-DIN") (pinfunction "DIN_4-DIN") (pintype "input"))
    )
    (net (code "37") (name "Net-(L30-DOUT)") (class "Default")
      (node (ref "L30") (pin "2-DOUT") (pinfunction "DOUT_2-DOUT") (pintype "output"))
      (node (ref "L31") (pin "4-DIN") (pinfunction "DIN_4-DIN") (pintype "input"))
    )
    (net (code "38") (name "Net-(L31-DOUT)") (class "Default")
      (node (ref "L31") (pin "2-DOUT") (pinfunction "DOUT_2-DOUT") (pintype "output"))
      (node (ref "L32") (pin "4-DIN") (pinfunction "DIN_4-DIN") (pintype "input"))
    )
    (net (code "39") (name "Net-(L32-DOUT)") (class "Default")
      (node (ref "L32") (pin "2-DOUT") (pinfunction "DOUT_2-DOUT") (pintype "output"))
      (node (ref "L33") (pin "4-DIN") (pinfunction "DIN_4-DIN") (pintype "input"))
    )
    (net (code "40") (name "Net-(L33-DOUT)") (class "Default")
      (node (ref "L33") (pin "2-DOUT") (pinfunction "DOUT_2-DOUT") (pintype "output"))
      (node (ref "L34") (pin "4-DIN") (pinfunction "DIN_4-DIN") (pintype "input"))
    )
    (net (code "41") (name "Net-(L34-DOUT)") (class "Default")
      (node (ref "L34") (pin "2-DOUT") (pinfunction "DOUT_2-DOUT") (pintype "output"))
      (node (ref "L35") (pin "4-DIN") (pinfunction "DIN_4-DIN") (pintype "input"))
    )
    (net (code "42") (name "Net-(L35-DOUT)") (class "Default")
      (node (ref "L35") (pin "2-DOUT") (pinfunction "DOUT_2-DOUT") (pintype "output"))
      (node (ref "L36") (pin "4-DIN") (pinfunction "DIN_4-DIN") (pintype "input"))
    )
    (net (code "43") (name "Net-(L36-DOUT)") (class "Default")
      (node (ref "L36") (pin "2-DOUT") (pinfunction "DOUT_2-DOUT") (pintype "output"))
      (node (ref "L37") (pin "4-DIN") (pinfunction "DIN_4-DIN") (pintype "input"))
    )
    (net (code "44") (name "Net-(L37-DOUT)") (class "Default")
      (node (ref "L37") (pin "2-DOUT") (pinfunction "DOUT_2-DOUT") (pintype "output"))
      (node (ref "L38") (pin "4-DIN") (pinfunction "DIN_4-DIN") (pintype "input"))
    )
    (net (code "45") (name "Net-(L38-DOUT)") (class "Default")
      (node (ref "L38") (pin "2-DOUT") (pinfunction "DOUT_2-DOUT") (pintype "output"))
      (node (ref "L39") (pin "4-DIN") (pinfunction "DIN_4-DIN") (pintype "input"))
    )
    (net (code "46") (name "Net-(L39-DOUT)") (class "Default")
      (node (ref "L39") (pin "2-DOUT") (pinfunction "DOUT_2-DOUT") (pintype "output"))
      (node (ref "L40") (pin "4-DIN") (pinfunction "DIN_4-DIN") (pintype "input"))
    )
    (net (code "47") (name "Net-(L40-DOUT)") (class "Default")
      (node (ref "L40") (pin "2-DOUT") (pinfunction "DOUT_2-DOUT") (pintype "output"))
      (node (ref "L41") (pin "4-DIN") (pinfunction "DIN_4-DIN") (pintype "input"))
    )
    (net (code "48") (name "Net-(L41-DOUT)") (class "Default")
      (node (ref "L41") (pin "2-DOUT") (pinfunction "DOUT_2-DOUT") (pintype "output"))
      (node (ref "L42") (pin "4-DIN") (pinfunction "DIN_4-DIN") (pintype "input"))
    )
    (net (code "49") (name "Net-(L42-DOUT)") (class "Default")
      (node (ref "L42") (pin "2-DOUT") (pinfunction "DOUT_2-DOUT") (pintype "output"))
      (node (ref "L43") (pin "4-DIN") (pinfunction "DIN_4-DIN") (pintype "input"))
    )
    (net (code "50") (name "Net-(L43-DOUT)") (class "Default")
      (node (ref "L43") (pin "2-DOUT") (pinfunction "DOUT_2-DOUT") (pintype "output"))
      (node (ref "L44") (pin "4-DIN") (pinfunction "DIN_4-DIN") (pintype "input"))
    )
    (net (code "51") (name "Net-(L44-DOUT)") (class "Default")
      (node (ref "L44") (pin "2-DOUT") (pinfunction "DOUT_2-DOUT") (pintype "output"))
      (node (ref "L45") (pin "4-DIN") (pinfunction "DIN_4-DIN") (pintype "input"))
    )
    (net (code "52") (name "Net-(L45-DOUT)") (class "Default")
      (node (ref "L45") (pin "2-DOUT") (pinfunction "DOUT_2-DOUT") (pintype "output"))
      (node (ref "L46") (pin "4-DIN") (pinfunction "DIN_4-DIN") (pintype "input"))
    )
    (net (code "53") (name "Net-(L46-DOUT)") (class "Default")
      (node (ref "L46") (pin "2-DOUT") (pinfunction "DOUT_2-DOUT") (pintype "output"))
      (node (ref "L47") (pin "4-DIN") (pinfunction "DIN_4-DIN") (pintype "input"))
    )
    (net (code "54") (name "Net-(L47-DOUT)") (class "Default")
      (node (ref "L47") (pin "2-DOUT") (pinfunction "DOUT_2-DOUT") (pintype "output"))
      (node (ref "L48") (pin "4-DIN") (pinfunction "DIN_4-DIN") (pintype "input"))
    )
    (net (code "55") (name "Net-(L48-DOUT)") (class "Default")
      (node (ref "L48") (pin "2-DOUT") (pinfunction "DOUT_2-DOUT") (pintype "output"))
      (node (ref "L49") (pin "4-DIN") (pinfunction "DIN_4-DIN") (pintype "input"))
    )
    (net (code "56") (name "Net-(L49-DOUT)") (class "Default")
      (node (ref "L49") (pin "2-DOUT") (pinfunction "DOUT_2-DOUT") (pintype "output"))
      (node (ref "L50") (pin "4-DIN") (pinfunction "DIN_4-DIN") (pintype "input"))
    )
    (net (code "57") (name "Net-(L50-DOUT)") (class "Default")
      (node (ref "L50") (pin "2-DOUT") (pinfunction "DOUT_2-DOUT") (pintype "output"))
      (node (ref "L51") (pin "4-DIN") (pinfunction "DIN_4-DIN") (pintype "input"))
    )
    (net (code "58") (name "Net-(L51-DOUT)") (class "Default")
      (node (ref "L51") (pin "2-DOUT") (pinfunction "DOUT_2-DOUT") (pintype "output"))
      (node (ref "L52") (pin "4-DIN") (pinfunction "DIN_4-DIN") (pintype "input"))
    )
    (net (code "59") (name "Net-(L52-DOUT)") (class "Default")
      (node (ref "L52") (pin "2-DOUT") (pinfunction "DOUT_2-DOUT") (pintype "output"))
      (node (ref "L53") (pin "4-DIN") (pinfunction "DIN_4-DIN") (pintype "input"))
    )
    (net (code "60") (name "Net-(L53-DOUT)") (class "Default")
      (node (ref "L53") (pin "2-DOUT") (pinfunction "DOUT_2-DOUT") (pintype "output"))
      (node (ref "L54") (pin "4-DIN") (pinfunction "DIN_4-DIN") (pintype "input"))
    )
    (net (code "61") (name "Net-(L54-DOUT)") (class "Default")
      (node (ref "L54") (pin "2-DOUT") (pinfunction "DOUT_2-DOUT") (pintype "output"))
      (node (ref "L55") (pin "4-DIN") (pinfunction "DIN_4-DIN") (pintype "input"))
    )
    (net (code "62") (name "Net-(L55-DOUT)") (class "Default")
      (node (ref "L55") (pin "2-DOUT") (pinfunction "DOUT_2-DOUT") (pintype "output"))
      (node (ref "L56") (pin "4-DIN") (pinfunction "DIN_4-DIN") (pintype "input"))
    )
    (net (code "63") (name "Net-(L56-DOUT)") (class "Default")
      (node (ref "L56") (pin "2-DOUT") (pinfunction "DOUT_2-DOUT") (pintype "output"))
      (node (ref "L57") (pin "4-DIN") (pinfunction "DIN_4-DIN") (pintype "input"))
    )
    (net (code "64") (name "Net-(L57-DOUT)") (class "Default")
      (node (ref "L57") (pin "2-DOUT") (pinfunction "DOUT_2-DOUT") (pintype "output"))
      (node (ref "L58") (pin "4-DIN") (pinfunction "DIN_4-DIN") (pintype "input"))
    )
    (net (code "65") (name "Net-(L58-DOUT)") (class "Default")
      (node (ref "L58") (pin "2-DOUT") (pinfunction "DOUT_2-DOUT") (pintype "output"))
      (node (ref "L59") (pin "4-DIN") (pinfunction "DIN_4-DIN") (pintype "input"))
    )
    (net (code "66") (name "Net-(L59-DOUT)") (class "Default")
      (node (ref "L59") (pin "2-DOUT") (pinfunction "DOUT_2-DOUT") (pintype "output"))
      (node (ref "L60") (pin "4-DIN") (pinfunction "DIN_4-DIN") (pintype "input"))
    )
    (net (code "67") (name "Net-(U1-PB3(ADC3))") (class "Default")
      (node (ref "S1") (pin "2") (pinfunction "2_2") (pintype "input"))
      (node (ref "U1") (pin "2") (pinfunction "PB3(ADC3)_2") (pintype "bidirectional"))
    )
    (net (code "68") (name "Net-(U1-PB4(ADC2))") (class "Default")
      (node (ref "R1") (pin "1") (pinfunction "1_1") (pintype "passive"))
      (node (ref "U1") (pin "3") (pinfunction "PB4(ADC2)_3") (pintype "bidirectional"))
    )
    (net (code "69") (name "Net-(U2-X1)") (class "Default")
      (node (ref "U2") (pin "1") (pinfunction "X1_1") (pintype "bidirectional"))
      (node (ref "X1") (pin "P$2") (pinfunction "P$2_P$2") (pintype "bidirectional"))
    )
    (net (code "70") (name "Net-(U2-X2)") (class "Default")
      (node (ref "U2") (pin "2") (pinfunction "X2_2") (pintype "bidirectional"))
      (node (ref "X1") (pin "P$1") (pinfunction "P$1_P$1") (pintype "bidirectional"))
    )
    (net (code "71") (name "VCC") (class "Default")
      (node (ref "C1") (pin "1") (pinfunction "1_1") (pintype "passive"))
      (node (ref "C10") (pin "1") (pinfunction "1_1") (pintype "passive"))
      (node (ref "C11") (pin "1") (pinfunction "1_1") (pintype "passive"))
      (node (ref "C12") (pin "1") (pinfunction "1_1") (pintype "passive"))
      (node (ref "C13") (pin "1") (pinfunction "1_1") (pintype "passive"))
      (node (ref "C14") (pin "1") (pinfunction "1_1") (pintype "passive"))
      (node (ref "C15") (pin "1") (pinfunction "1_1") (pintype "passive"))
      (node (ref "C16") (pin "1") (pinfunction "1_1") (pintype "passive"))
      (node (ref "C17") (pin "1") (pinfunction "1_1") (pintype "passive"))
      (node (ref "C18") (pin "1") (pinfunction "1_1") (pintype "passive"))
      (node (ref "C19") (pin "1") (pinfunction "1_1") (pintype "passive"))
      (node (ref "C2") (pin "1") (pinfunction "1_1") (pintype "passive"))
      (node (ref "C20") (pin "1") (pinfunction "1_1") (pintype "passive"))
      (node (ref "C21") (pin "1") (pinfunction "1_1") (pintype "passive"))
      (node (ref "C22") (pin "1") (pinfunction "1_1") (pintype "passive"))
      (node (ref "C23") (pin "1") (pinfunction "1_1") (pintype "passive"))
      (node (ref "C24") (pin "1") (pinfunction "1_1") (pintype "passive"))
      (node (ref "C25") (pin "1") (pinfunction "1_1") (pintype "passive"))
      (node (ref "C26") (pin "1") (pinfunction "1_1") (pintype "passive"))
      (node (ref "C27") (pin "1") (pinfunction "1_1") (pintype "passive"))
      (node (ref "C28") (pin "1") (pinfunction "1_1") (pintype "passive"))
      (node (ref "C29") (pin "1") (pinfunction "1_1") (pintype "passive"))
      (node (ref "C3") (pin "1") (pinfunction "1_1") (pintype "passive"))
      (node (ref "C30") (pin "1") (pinfunction "1_1") (pintype "passive"))
      (node (ref "C31") (pin "1") (pinfunction "1_1") (pintype "passive"))
      (node (ref "C32") (pin "1") (pinfunction "1_1") (pintype "passive"))
      (node (ref "C33") (pin "1") (pinfunction "1_1") (pintype "passive"))
      (node (ref "C34") (pin "1") (pinfunction "1_1") (pintype "passive"))
      (node (ref "C35") (pin "1") (pinfunction "1_1") (pintype "passive"))
      (node (ref "C36") (pin "1") (pinfunction "1_1") (pintype "passive"))
      (node (ref "C37") (pin "1") (pinfunction "1_1") (pintype "passive"))
      (node (ref "C38") (pin "1") (pinfunction "1_1") (pintype "passive"))
      (node (ref "C39") (pin "1") (pinfunction "1_1") (pintype "passive"))
      (node (ref "C4") (pin "1") (pinfunction "1_1") (pintype "passive"))
      (node (ref "C40") (pin "1") (pinfunction "1_1") (pintype "passive"))
      (node (ref "C41") (pin "1") (pinfunction "1_1") (pintype "passive"))
      (node (ref "C42") (pin "1") (pinfunction "1_1") (pintype "passive"))
      (node (ref "C43") (pin "1") (pinfunction "1_1") (pintype "passive"))
      (node (ref "C44") (pin "1") (pinfunction "1_1") (pintype "passive"))
      (node (ref "C45") (pin "1") (pinfunction "1_1") (pintype "passive"))
      (node (ref "C46") (pin "1") (pinfunction "1_1") (pintype "passive"))
      (node (ref "C47") (pin "1") (pinfunction "1_1") (pintype "passive"))
      (node (ref "C48") (pin "1") (pinfunction "1_1") (pintype "passive"))
      (node (ref "C49") (pin "1") (pinfunction "1_1") (pintype "passive"))
      (node (ref "C5") (pin "1") (pinfunction "1_1") (pintype "passive"))
      (node (ref "C50") (pin "1") (pinfunction "1_1") (pintype "passive"))
      (node (ref "C51") (pin "1") (pinfunction "1_1") (pintype "passive"))
      (node (ref "C52") (pin "1") (pinfunction "1_1") (pintype "passive"))
      (node (ref "C7") (pin "1") (pinfunction "1_1") (pintype "passive"))
      (node (ref "C8") (pin "1") (pinfunction "1_1") (pintype "passive"))
      (node (ref "C9") (pin "1") (pinfunction "1_1") (pintype "passive"))
      (node (ref "ISP") (pin "2") (pinfunction "VCC_2") (pintype "power_in"))
      (node (ref "JP2") (pin "1") (pinfunction "VCC_1") (pintype "bidirectional"))
      (node (ref "L1") (pin "1-VDD") (pinfunction "VDD_1-VDD") (pintype "bidirectional"))
      (node (ref "L10") (pin "1-VDD") (pinfunction "VDD_1-VDD") (pintype "bidirectional"))
      (node (ref "L11") (pin "1-VDD") (pinfunction "VDD_1-VDD") (pintype "bidirectional"))
      (node (ref "L12") (pin "1-VDD") (pinfunction "VDD_1-VDD") (pintype "bidirectional"))
      (node (ref "L13") (pin "1-VDD") (pinfunction "VDD_1-VDD") (pintype "bidirectional"))
      (node (ref "L14") (pin "1-VDD") (pinfunction "VDD_1-VDD") (pintype "bidirectional"))
      (node (ref "L15") (pin "1-VDD") (pinfunction "VDD_1-VDD") (pintype "bidirectional"))
      (node (ref "L16") (pin "1-VDD") (pinfunction "VDD_1-VDD") (pintype "bidirectional"))
      (node (ref "L17") (pin "1-VDD") (pinfunction "VDD_1-VDD") (pintype "bidirectional"))
      (node (ref "L18") (pin "1-VDD") (pinfunction "VDD_1-VDD") (pintype "bidirectional"))
      (node (ref "L19") (pin "1-VDD") (pinfunction "VDD_1-VDD") (pintype "bidirectional"))
      (node (ref "L2") (pin "1-VDD") (pinfunction "VDD_1-VDD") (pintype "bidirectional"))
      (node (ref "L20") (pin "1-VDD") (pinfunction "VDD_1-VDD") (pintype "bidirectional"))
      (node (ref "L21") (pin "1-VDD") (pinfunction "VDD_1-VDD") (pintype "bidirectional"))
      (node (ref "L22") (pin "1-VDD") (pinfunction "VDD_1-VDD") (pintype "bidirectional"))
      (node (ref "L23") (pin "1-VDD") (pinfunction "VDD_1-VDD") (pintype "bidirectional"))
      (node (ref "L24") (pin "1-VDD") (pinfunction "VDD_1-VDD") (pintype "bidirectional"))
      (node (ref "L25") (pin "1-VDD") (pinfunction "VDD_1-VDD") (pintype "bidirectional"))
      (node (ref "L26") (pin "1-VDD") (pinfunction "VDD_1-VDD") (pintype "bidirectional"))
      (node (ref "L27") (pin "1-VDD") (pinfunction "VDD_1-VDD") (pintype "bidirectional"))
      (node (ref "L28") (pin "1-VDD") (pinfunction "VDD_1-VDD") (pintype "bidirectional"))
      (node (ref "L29") (pin "1-VDD") (pinfunction "VDD_1-VDD") (pintype "bidirectional"))
      (node (ref "L3") (pin "1-VDD") (pinfunction "VDD_1-VDD") (pintype "bidirectional"))
      (node (ref "L30") (pin "1-VDD") (pinfunction "VDD_1-VDD") (pintype "bidirectional"))
      (node (ref "L31") (pin "1-VDD") (pinfunction "VDD_1-VDD") (pintype "bidirectional"))
      (node (ref "L32") (pin "1-VDD") (pinfunction "VDD_1-VDD") (pintype "bidirectional"))
      (node (ref "L33") (pin "1-VDD") (pinfunction "VDD_1-VDD") (pintype "bidirectional"))
      (node (ref "L34") (pin "1-VDD") (pinfunction "VDD_1-VDD") (pintype "bidirectional"))
      (node (ref "L35") (pin "1-VDD") (pinfunction "VDD_1-VDD") (pintype "bidirectional"))
      (node (ref "L36") (pin "1-VDD") (pinfunction "VDD_1-VDD") (pintype "bidirectional"))
      (node (ref "L37") (pin "1-VDD") (pinfunction "VDD_1-VDD") (pintype "bidirectional"))
      (node (ref "L38") (pin "1-VDD") (pinfunction "VDD_1-VDD") (pintype "bidirectional"))
      (node (ref "L39") (pin "1-VDD") (pinfunction "VDD_1-VDD") (pintype "bidirectional"))
      (node (ref "L4") (pin "1-VDD") (pinfunction "VDD_1-VDD") (pintype "bidirectional"))
      (node (ref "L40") (pin "1-VDD") (pinfunction "VDD_1-VDD") (pintype "bidirectional"))
      (node (ref "L41") (pin "1-VDD") (pinfunction "VDD_1-VDD") (pintype "bidirectional"))
      (node (ref "L42") (pin "1-VDD") (pinfunction "VDD_1-VDD") (pintype "bidirectional"))
      (node (ref "L43") (pin "1-VDD") (pinfunction "VDD_1-VDD") (pintype "bidirectional"))
      (node (ref "L44") (pin "1-VDD") (pinfunction "VDD_1-VDD") (pintype "bidirectional"))
      (node (ref "L45") (pin "1-VDD") (pinfunction "VDD_1-VDD") (pintype "bidirectional"))
      (node (ref "L46") (pin "1-VDD") (pinfunction "VDD_1-VDD") (pintype "bidirectional"))
      (node (ref "L47") (pin "1-VDD") (pinfunction "VDD_1-VDD") (pintype "bidirectional"))
      (node (ref "L48") (pin "1-VDD") (pinfunction "VDD_1-VDD") (pintype "bidirectional"))
      (node (ref "L49") (pin "1-VDD") (pinfunction "VDD_1-VDD") (pintype "bidirectional"))
      (node (ref "L5") (pin "1-VDD") (pinfunction "VDD_1-VDD") (pintype "bidirectional"))
      (node (ref "L50") (pin "1-VDD") (pinfunction "VDD_1-VDD") (pintype "bidirectional"))
      (node (ref "L51") (pin "1-VDD") (pinfunction "VDD_1-VDD") (pintype "bidirectional"))
      (node (ref "L52") (pin "1-VDD") (pinfunction "VDD_1-VDD") (pintype "bidirectional"))
      (node (ref "L53") (pin "1-VDD") (pinfunction "VDD_1-VDD") (pintype "bidirectional"))
      (node (ref "L54") (pin "1-VDD") (pinfunction "VDD_1-VDD") (pintype "bidirectional"))
      (node (ref "L55") (pin "1-VDD") (pinfunction "VDD_1-VDD") (pintype "bidirectional"))
      (node (ref "L56") (pin "1-VDD") (pinfunction "VDD_1-VDD") (pintype "bidirectional"))
      (node (ref "L57") (pin "1-VDD") (pinfunction "VDD_1-VDD") (pintype "bidirectional"))
      (node (ref "L58") (pin "1-VDD") (pinfunction "VDD_1-VDD") (pintype "bidirectional"))
      (node (ref "L59") (pin "1-VDD") (pinfunction "VDD_1-VDD") (pintype "bidirectional"))
      (node (ref "L6") (pin "1-VDD") (pinfunction "VDD_1-VDD") (pintype "bidirectional"))
      (node (ref "L60") (pin "1-VDD") (pinfunction "VDD_1-VDD") (pintype "bidirectional"))
      (node (ref "L7") (pin "1-VDD") (pinfunction "VDD_1-VDD") (pintype "bidirectional"))
      (node (ref "L8") (pin "1-VDD") (pinfunction "VDD_1-VDD") (pintype "bidirectional"))
      (node (ref "L9") (pin "1-VDD") (pinfunction "VDD_1-VDD") (pintype "bidirectional"))
      (node (ref "R2") (pin "2") (pinfunction "2_2") (pintype "passive"))
      (node (ref "R3") (pin "2") (pinfunction "2_2") (pintype "passive"))
      (node (ref "U1") (pin "8") (pinfunction "VCC_8") (pintype "bidirectional"))
      (node (ref "U2") (pin "8") (pinfunction "VCC_8") (pintype "bidirectional"))
    )
    (net (code "72") (name "unconnected-(JP2-D+-Pad3)") (class "Default")
      (node (ref "JP2") (pin "3") (pinfunction "D+_3") (pintype "bidirectional"))
    )
    (net (code "73") (name "unconnected-(JP2-D--Pad2)") (class "Default")
      (node (ref "JP2") (pin "2") (pinfunction "D-_2") (pintype "bidirectional"))
    )
    (net (code "74") (name "unconnected-(JP2-ID-Pad4)") (class "Default")
      (node (ref "JP2") (pin "4") (pinfunction "ID_4") (pintype "bidirectional"))
    )
    (net (code "75") (name "unconnected-(L60-DOUT-Pad2-DOUT)") (class "Default")
      (node (ref "L60") (pin "2-DOUT") (pinfunction "DOUT_2-DOUT") (pintype "output"))
    )
    (net (code "76") (name "unconnected-(U2-SQW-Pad7)") (class "Default")
      (node (ref "U2") (pin "7") (pinfunction "SQW_7") (pintype "bidirectional"))
    )
  )
)
